# Power_Card.net
KiCad netlist of a schematic drawn in Altium Designer
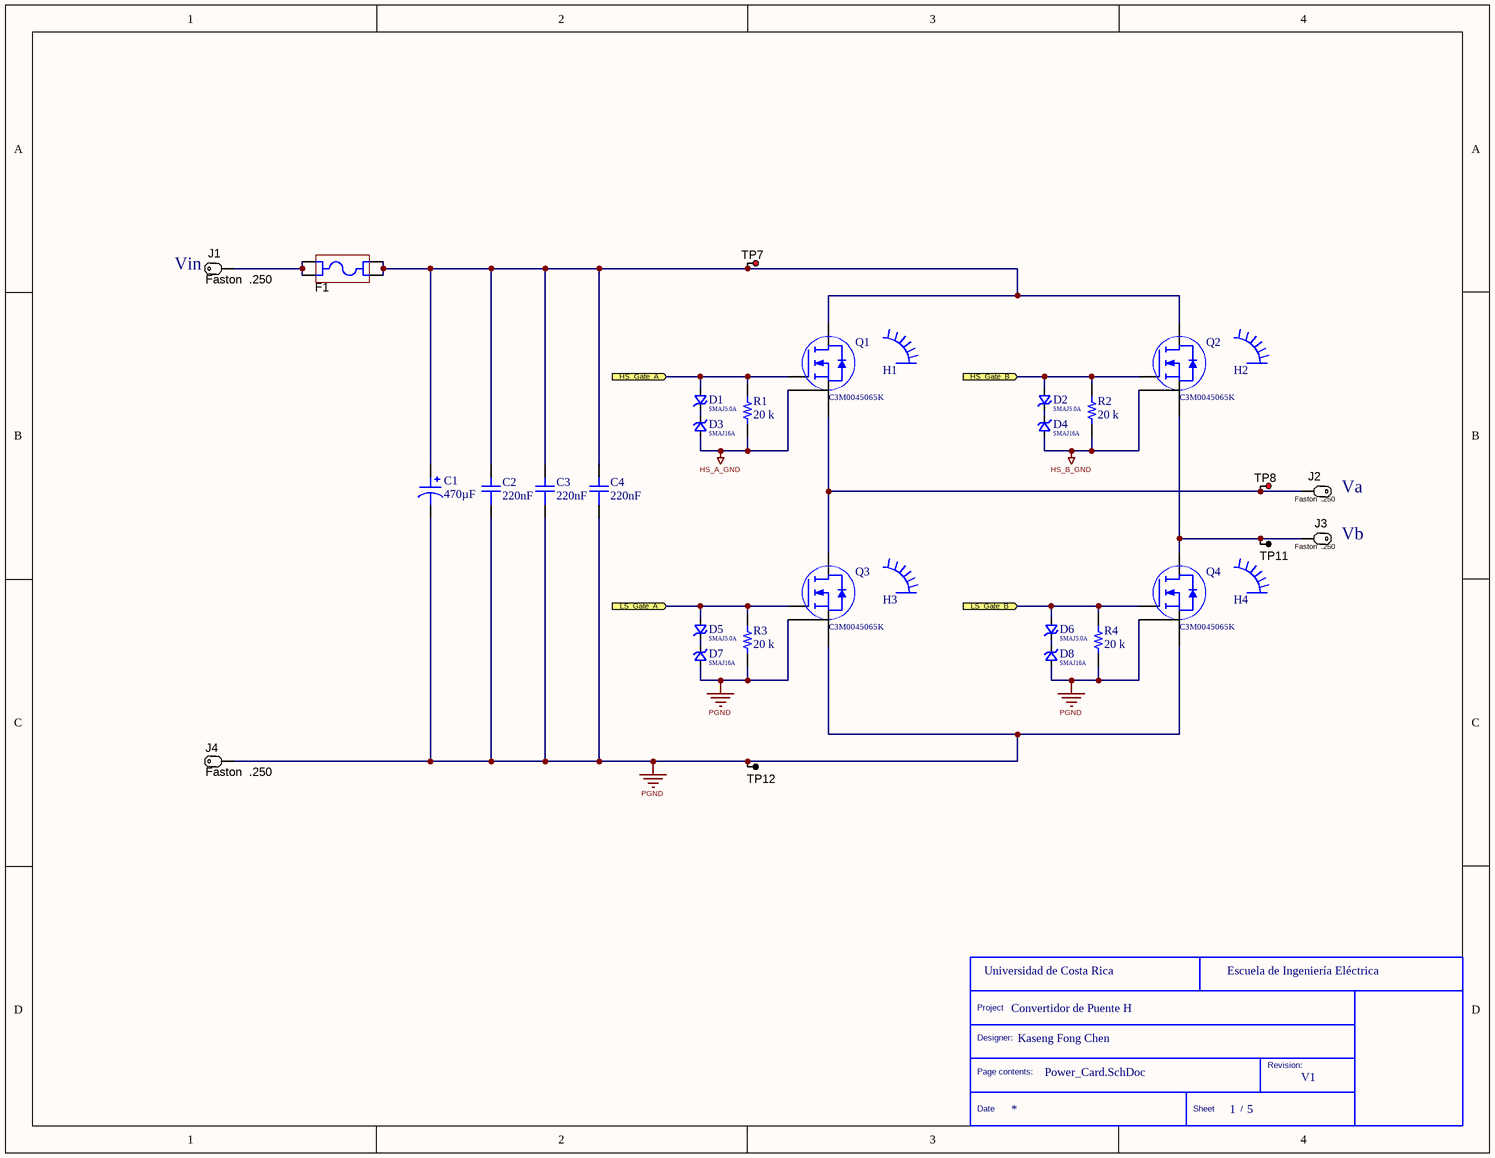
[diagram p0: Power_Card.SchDoc]

(export (version "E")
  (design (tool "Eeschema 10.0.6"))
  (components
    (comp (ref "C1")
      (value "470µF")
      (footprint "CAP TH ALUM ELEC D35.00mm S10.00mm H40.00mm")
      (description "CAP ALUM 470UF 20% 450V SNAP")
      (fields
        (field (name "PART NUMBER") "ESMQ451VSN471MA40S")
        (field (name "MANUFACTURER") "United Chemi-Con")
      )
      (libsource (lib "Celestial Altium Library - altium_library") (part "Polarised Capacitor"))
    )
    (comp (ref "C2")
      (value "220nF")
      (footprint "R75PI32204030J")
      (fields
        (field (name "MANUFACTURER") "KEMET")
        (field (name "MANUFACTURER PART NUMBER") "R75PI32204030J")
        (field (name "TOLERANCE") "5%")
      )
      (libsource (lib "kasengLib") (part "R75PI32204030J"))
    )
    (comp (ref "C3")
      (value "220nF")
      (footprint "R75PI32204030J")
      (fields
        (field (name "MANUFACTURER") "KEMET")
        (field (name "MANUFACTURER PART NUMBER") "R75PI32204030J")
        (field (name "TOLERANCE") "5%")
      )
      (libsource (lib "kasengLib") (part "R75PI32204030J"))
    )
    (comp (ref "C4")
      (value "220nF")
      (footprint "R75PI32204030J")
      (fields
        (field (name "MANUFACTURER") "KEMET")
        (field (name "MANUFACTURER PART NUMBER") "R75PI32204030J")
        (field (name "TOLERANCE") "5%")
      )
      (libsource (lib "kasengLib") (part "R75PI32204030J"))
    )
    (comp (ref "D1")
      (value "SMAJ5.0A")
      (footprint "DO214AC SMA")
      (description "BOURNS - SMAJ5.0A - TVS Diode, SMAJ Series, Unidirectional, 5 V, 9.2 V, DO-214AC (SMA), 2 Pins")
      (fields (field (name "MANUFACTURER") "Bourns"))
      (libsource (lib "KasengLIb") (part "SMAJ5.0A"))
    )
    (comp (ref "D2")
      (value "SMAJ5.0A")
      (footprint "DO214AC SMA")
      (description "BOURNS - SMAJ5.0A - TVS Diode, SMAJ Series, Unidirectional, 5 V, 9.2 V, DO-214AC (SMA), 2 Pins")
      (fields (field (name "MANUFACTURER") "Bourns"))
      (libsource (lib "KasengLIb") (part "SMAJ5.0A"))
    )
    (comp (ref "D3")
      (value "SMAJ16A")
      (footprint "DO214AC SMA")
      (description "TVS DIODE 16VWM 26VC DO214AC")
      (fields (field (name "MANUFACTURER") "Bourns"))
      (libsource (lib "KasengLIb") (part "SMAJ16A"))
    )
    (comp (ref "D4")
      (value "SMAJ16A")
      (footprint "DO214AC SMA")
      (description "TVS DIODE 16VWM 26VC DO214AC")
      (fields (field (name "MANUFACTURER") "Bourns"))
      (libsource (lib "KasengLIb") (part "SMAJ16A"))
    )
    (comp (ref "D5")
      (value "SMAJ5.0A")
      (footprint "DO214AC SMA")
      (description "BOURNS - SMAJ5.0A - TVS Diode, SMAJ Series, Unidirectional, 5 V, 9.2 V, DO-214AC (SMA), 2 Pins")
      (fields (field (name "MANUFACTURER") "Bourns"))
      (libsource (lib "KasengLIb") (part "SMAJ5.0A"))
    )
    (comp (ref "D6")
      (value "SMAJ5.0A")
      (footprint "DO214AC SMA")
      (description "BOURNS - SMAJ5.0A - TVS Diode, SMAJ Series, Unidirectional, 5 V, 9.2 V, DO-214AC (SMA), 2 Pins")
      (fields (field (name "MANUFACTURER") "Bourns"))
      (libsource (lib "KasengLIb") (part "SMAJ5.0A"))
    )
    (comp (ref "D7")
      (value "SMAJ16A")
      (footprint "DO214AC SMA")
      (description "TVS DIODE 16VWM 26VC DO214AC")
      (fields (field (name "MANUFACTURER") "Bourns"))
      (libsource (lib "KasengLIb") (part "SMAJ16A"))
    )
    (comp (ref "D8")
      (value "SMAJ16A")
      (footprint "DO214AC SMA")
      (description "TVS DIODE 16VWM 26VC DO214AC")
      (fields (field (name "MANUFACTURER") "Bourns"))
      (libsource (lib "KasengLIb") (part "SMAJ16A"))
    )
    (comp (ref "F1")
      (value "3101.0040")
      (footprint "SCHURTER_3101_0040")
      (description "Fuse Holder, 400 V, 16 A, TH")
      (fields
        (field (name "MANUFACTURER") "Schurter")
        (field (name "SYMBOLCREATOR") "a0799628")
        (field (name "PUBLISHER") "Texas Instruments")
      )
      (libsource (lib "kasengLib") (part "3101.0040"))
    )
    (comp (ref "H1")
      (value "Disipador de 3.3.C/W")
      (footprint "HSINK_6399BG")
      (fields
        (field (name "MANUFACTURER") "Aavid Thermalloy")
        (field (name "MANUFACTURER PART NUMBER") "6399BG")
      )
      (libsource (lib "kasengLib") (part "6399BG"))
    )
    (comp (ref "H2")
      (value "Disipador de 3.3.C/W")
      (footprint "HSINK_6399BG")
      (fields
        (field (name "MANUFACTURER") "Aavid Thermalloy")
        (field (name "MANUFACTURER PART NUMBER") "6399BG")
      )
      (libsource (lib "kasengLib") (part "6399BG"))
    )
    (comp (ref "H3")
      (value "Disipador de 3.3.C/W")
      (footprint "HSINK_6399BG")
      (fields
        (field (name "MANUFACTURER") "Aavid Thermalloy")
        (field (name "MANUFACTURER PART NUMBER") "6399BG")
      )
      (libsource (lib "kasengLib") (part "6399BG"))
    )
    (comp (ref "H4")
      (value "Disipador de 3.3.C/W")
      (footprint "HSINK_6399BG")
      (fields
        (field (name "MANUFACTURER") "Aavid Thermalloy")
        (field (name "MANUFACTURER PART NUMBER") "6399BG")
      )
      (libsource (lib "kasengLib") (part "6399BG"))
    )
    (comp (ref "J1")
      (value "Faston  .250")
      (footprint "TE_62409-1")
      (description "Quick Disconnect Terminal M 15.8mm 7.5mm Tin Over Copper Automotive Bag")
      (fields
        (field (name "MANUFACTURER") "AMP - TE CONNECTIVITY")
        (field (name "MANUFACTURER PART NUMBER") "62409-1")
      )
      (libsource (lib "kasengLib") (part "62409-1"))
    )
    (comp (ref "J2")
      (value "Faston  .250")
      (footprint "TE_62409-1")
      (description "Quick Disconnect Terminal M 15.8mm 7.5mm Tin Over Copper Automotive Bag")
      (fields
        (field (name "MANUFACTURER") "AMP - TE CONNECTIVITY")
        (field (name "MANUFACTURER PART NUMBER") "62409-1")
      )
      (libsource (lib "kasengLib") (part "62409-1"))
    )
    (comp (ref "J3")
      (value "Faston  .250")
      (footprint "TE_62409-1")
      (description "Quick Disconnect Terminal M 15.8mm 7.5mm Tin Over Copper Automotive Bag")
      (fields
        (field (name "MANUFACTURER") "AMP - TE CONNECTIVITY")
        (field (name "MANUFACTURER PART NUMBER") "62409-1")
      )
      (libsource (lib "kasengLib") (part "62409-1"))
    )
    (comp (ref "J4")
      (value "Faston  .250")
      (footprint "TE_62409-1")
      (description "Quick Disconnect Terminal M 15.8mm 7.5mm Tin Over Copper Automotive Bag")
      (fields
        (field (name "MANUFACTURER") "AMP - TE CONNECTIVITY")
        (field (name "MANUFACTURER PART NUMBER") "62409-1")
      )
      (libsource (lib "kasengLib") (part "62409-1"))
    )
    (comp (ref "Q1")
      (value "C3M0045065K")
      (footprint "TO-247-4L_C3M0075120K_WFS")
      (description "Sic MOSFET 650V")
      (fields (field (name "MANUFACTURER") "Cree Wolfspeed"))
      (libsource (lib "kasengLib") (part "C3M0045065K"))
    )
    (comp (ref "Q2")
      (value "C3M0045065K")
      (footprint "TO-247-4L_C3M0075120K_WFS")
      (description "Sic MOSFET 650V")
      (fields (field (name "MANUFACTURER") "Cree Wolfspeed"))
      (libsource (lib "kasengLib") (part "C3M0045065K"))
    )
    (comp (ref "Q3")
      (value "C3M0045065K")
      (footprint "TO-247-4L_C3M0075120K_WFS")
      (description "Sic MOSFET 650V")
      (fields (field (name "MANUFACTURER") "Cree Wolfspeed"))
      (libsource (lib "kasengLib") (part "C3M0045065K"))
    )
    (comp (ref "Q4")
      (value "C3M0045065K")
      (footprint "TO-247-4L_C3M0075120K_WFS")
      (description "Sic MOSFET 650V")
      (fields (field (name "MANUFACTURER") "Cree Wolfspeed"))
      (libsource (lib "kasengLib") (part "C3M0045065K"))
    )
    (comp (ref "R1")
      (value "20 k")
      (footprint "RES 0603_1608")
      (description "RES SMD 20K OHM 1% 1/10W 0603")
      (fields (field (name "PART NUMBER") "RC0603FR-0720KL") (field (name "MANUFACTURER") "Yageo"))
      (libsource (lib "Celestial Altium Library - altium_library") (part "Resistor"))
    )
    (comp (ref "R2")
      (value "20 k")
      (footprint "RES 0603_1608")
      (description "RES SMD 20K OHM 1% 1/10W 0603")
      (fields (field (name "PART NUMBER") "RC0603FR-0720KL") (field (name "MANUFACTURER") "Yageo"))
      (libsource (lib "Celestial Altium Library - altium_library") (part "Resistor"))
    )
    (comp (ref "R3")
      (value "20 k")
      (footprint "RES 0603_1608")
      (description "RES SMD 20K OHM 1% 1/10W 0603")
      (fields (field (name "PART NUMBER") "RC0603FR-0720KL") (field (name "MANUFACTURER") "Yageo"))
      (libsource (lib "Celestial Altium Library - altium_library") (part "Resistor"))
    )
    (comp (ref "R4")
      (value "20 k")
      (footprint "RES 0603_1608")
      (description "RES SMD 20K OHM 1% 1/10W 0603")
      (fields (field (name "PART NUMBER") "RC0603FR-0720KL") (field (name "MANUFACTURER") "Yageo"))
      (libsource (lib "Celestial Altium Library - altium_library") (part "Resistor"))
    )
    (comp (ref "TP7")
      (value "5010")
      (footprint "Keystone5010")
      (description "Test Point, Multipurpose, Red, TH")
      (fields (field (name "MANUFACTURER") "Keystone") (field (name "PUBLISHER") "Texas Instruments"))
      (libsource (lib "kasengLib") (part "5010"))
    )
    (comp (ref "TP8")
      (value "5010")
      (footprint "Keystone5010")
      (description "Test Point, Multipurpose, Red, TH")
      (fields (field (name "MANUFACTURER") "Keystone") (field (name "PUBLISHER") "Texas Instruments"))
      (libsource (lib "kasengLib") (part "5010"))
    )
    (comp (ref "TP11")
      (value "5011")
      (footprint "Keystone5011")
      (description "Test Point, Multipurpose, Black, TH")
      (fields (field (name "MANUFACTURER") "Keystone") (field (name "PUBLISHER") "Texas Instruments"))
      (libsource (lib "kasengLib") (part "5011"))
    )
    (comp (ref "TP12")
      (value "5011")
      (footprint "Keystone5011")
      (description "Test Point, Multipurpose, Black, TH")
      (fields (field (name "MANUFACTURER") "Keystone") (field (name "PUBLISHER") "Texas Instruments"))
      (libsource (lib "kasengLib") (part "5011"))
    )
  )
  (nets
    (net (code "1") (name "/HS_Gate_A") (class "Default")
      (node (ref "D1") (pin "2") (pinfunction "2_2") (pintype "passive"))
      (node (ref "Q1") (pin "4") (pinfunction "G_4") (pintype "passive"))
      (node (ref "R1") (pin "2") (pinfunction "2_2") (pintype "passive"))
    )
    (net (code "2") (name "/HS_Gate_B") (class "Default")
      (node (ref "D2") (pin "2") (pinfunction "2_2") (pintype "passive"))
      (node (ref "Q2") (pin "4") (pinfunction "G_4") (pintype "passive"))
      (node (ref "R2") (pin "2") (pinfunction "2_2") (pintype "passive"))
    )
    (net (code "3") (name "/LS_Gate_A") (class "Default")
      (node (ref "D5") (pin "2") (pinfunction "2_2") (pintype "passive"))
      (node (ref "Q3") (pin "4") (pinfunction "G_4") (pintype "passive"))
      (node (ref "R3") (pin "2") (pinfunction "2_2") (pintype "passive"))
    )
    (net (code "4") (name "/LS_Gate_B") (class "Default")
      (node (ref "D6") (pin "2") (pinfunction "2_2") (pintype "passive"))
      (node (ref "Q4") (pin "4") (pinfunction "G_4") (pintype "passive"))
      (node (ref "R4") (pin "2") (pinfunction "2_2") (pintype "passive"))
    )
    (net (code "5") (name "HS_A_GND") (class "Default")
      (node (ref "D3") (pin "2") (pinfunction "2_2") (pintype "passive"))
      (node (ref "Q1") (pin "3") (pinfunction "S_3") (pintype "passive"))
      (node (ref "R1") (pin "1") (pinfunction "1_1") (pintype "passive"))
    )
    (net (code "6") (name "HS_B_GND") (class "Default")
      (node (ref "D4") (pin "2") (pinfunction "2_2") (pintype "passive"))
      (node (ref "Q2") (pin "3") (pinfunction "S_3") (pintype "passive"))
      (node (ref "R2") (pin "1") (pinfunction "1_1") (pintype "passive"))
    )
    (net (code "7") (name "Net-(D1-Pad1)") (class "Default")
      (node (ref "D1") (pin "1") (pinfunction "1_1") (pintype "passive"))
      (node (ref "D3") (pin "1") (pinfunction "1_1") (pintype "passive"))
    )
    (net (code "8") (name "Net-(D2-Pad1)") (class "Default")
      (node (ref "D2") (pin "1") (pinfunction "1_1") (pintype "passive"))
      (node (ref "D4") (pin "1") (pinfunction "1_1") (pintype "passive"))
    )
    (net (code "9") (name "Net-(D5-Pad1)") (class "Default")
      (node (ref "D5") (pin "1") (pinfunction "1_1") (pintype "passive"))
      (node (ref "D7") (pin "1") (pinfunction "1_1") (pintype "passive"))
    )
    (net (code "10") (name "Net-(D6-Pad1)") (class "Default")
      (node (ref "D6") (pin "1") (pinfunction "1_1") (pintype "passive"))
      (node (ref "D8") (pin "1") (pinfunction "1_1") (pintype "passive"))
    )
    (net (code "11") (name "Net-(J1-P1)") (class "Default")
      (node (ref "F1") (pin "1") (pinfunction "1_1") (pintype "passive"))
      (node (ref "F1") (pin "2") (pinfunction "2_2") (pintype "passive"))
      (node (ref "J1") (pin "1") (pinfunction "P1_1") (pintype "passive"))
    )
    (net (code "12") (name "Net-(J2-P1)") (class "Default")
      (node (ref "J2") (pin "1") (pinfunction "P1_1") (pintype "passive"))
      (node (ref "Q1") (pin "2") (pinfunction "Power_Source_2") (pintype "passive"))
      (node (ref "Q3") (pin "1") (pinfunction "D_1") (pintype "passive"))
      (node (ref "TP8") (pin "1") (pinfunction "1_1") (pintype "passive"))
    )
    (net (code "13") (name "Net-(J3-P1)") (class "Default")
      (node (ref "J3") (pin "1") (pinfunction "P1_1") (pintype "passive"))
      (node (ref "Q2") (pin "2") (pinfunction "Power_Source_2") (pintype "passive"))
      (node (ref "Q4") (pin "1") (pinfunction "D_1") (pintype "passive"))
      (node (ref "TP11") (pin "1") (pinfunction "1_1") (pintype "passive"))
    )
    (net (code "14") (name "Net-(Q1-D)") (class "Default")
      (node (ref "C1") (pin "1") (pinfunction "1_1") (pintype "passive"))
      (node (ref "C2") (pin "1") (pinfunction "1_1") (pintype "passive"))
      (node (ref "C3") (pin "1") (pinfunction "1_1") (pintype "passive"))
      (node (ref "C4") (pin "1") (pinfunction "1_1") (pintype "passive"))
      (node (ref "F1") (pin "3") (pinfunction "3_3") (pintype "passive"))
      (node (ref "F1") (pin "4") (pinfunction "4_4") (pintype "passive"))
      (node (ref "Q1") (pin "1") (pinfunction "D_1") (pintype "passive"))
      (node (ref "Q2") (pin "1") (pinfunction "D_1") (pintype "passive"))
      (node (ref "TP7") (pin "1") (pinfunction "1_1") (pintype "passive"))
    )
    (net (code "15") (name "PGND") (class "Default")
      (node (ref "C1") (pin "2") (pinfunction "2_2") (pintype "passive"))
      (node (ref "C2") (pin "2") (pinfunction "2_2") (pintype "passive"))
      (node (ref "C3") (pin "2") (pinfunction "2_2") (pintype "passive"))
      (node (ref "C4") (pin "2") (pinfunction "2_2") (pintype "passive"))
      (node (ref "D7") (pin "2") (pinfunction "2_2") (pintype "passive"))
      (node (ref "D8") (pin "2") (pinfunction "2_2") (pintype "passive"))
      (node (ref "J4") (pin "1") (pinfunction "P1_1") (pintype "passive"))
      (node (ref "Q3") (pin "2") (pinfunction "Power_Source_2") (pintype "passive"))
      (node (ref "Q3") (pin "3") (pinfunction "S_3") (pintype "passive"))
      (node (ref "Q4") (pin "2") (pinfunction "Power_Source_2") (pintype "passive"))
      (node (ref "Q4") (pin "3") (pinfunction "S_3") (pintype "passive"))
      (node (ref "R3") (pin "1") (pinfunction "1_1") (pintype "passive"))
      (node (ref "R4") (pin "1") (pinfunction "1_1") (pintype "passive"))
      (node (ref "TP12") (pin "1") (pinfunction "1_1") (pintype "passive"))
    )
  )
)
